# litterbox.net
KiCad netlist of a schematic drawn in EAGLE
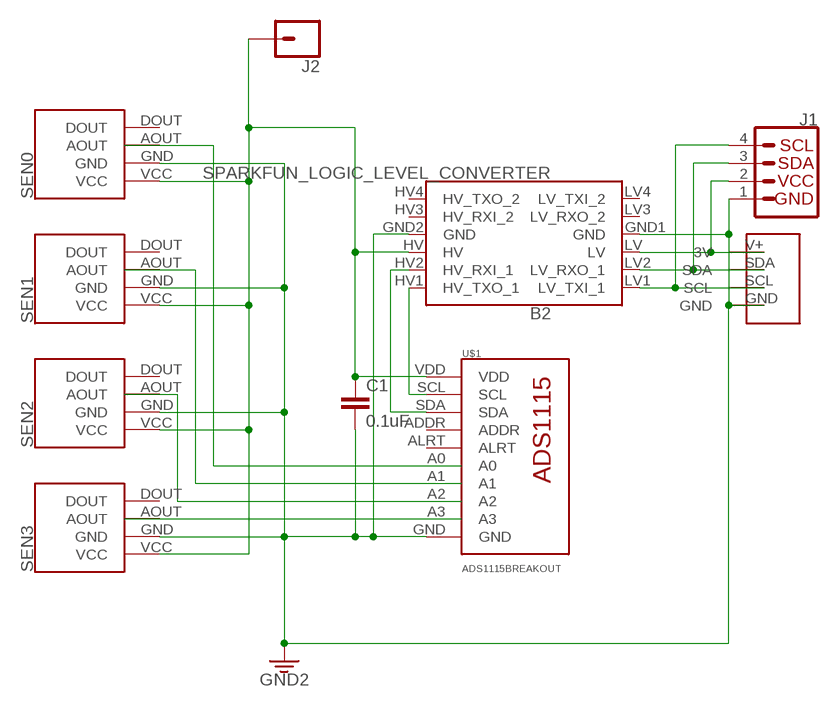
[diagram p0: schematic, sheet 1]

(export (version "E")
  (design (tool "Eeschema 10.0.6"))
  (components
    (comp (ref "B2")
      (value "SPARKFUN_LOGIC_LEVEL_CONVERTER")
      (footprint "eagle-import:SPARKFUN_LOGIC_LEVEL_CONVERTER")
      (libsource (lib "eagle-import") (part "SPARKFUN_LOGIC_LEVEL_CONVERTER"))
    )
    (comp (ref "C1")
      (value "0.1uF")
      (footprint "eagle-import:CAP-PTH-SMALL-KIT")
      (libsource (lib "eagle-import") (part "0.1UF-KIT-EZ-50V-20%"))
    )
    (comp (ref "J1")
      (value "QWIIC_CONNECTORJS-1MM")
      (footprint "eagle-import:1X04_1MM_RA")
      (libsource (lib "eagle-import") (part "QWIIC_CONNECTORJS-1MM"))
    )
    (comp (ref "J2")
      (value "CONN_01")
      (footprint "eagle-import:1X01")
      (libsource (lib "eagle-import") (part "CONN_01"))
    )
    (comp (ref "SEN0")
      (value "MQ-SENSOR-BREAKOUT")
      (footprint "eagle-import:MQ-SENSOR-BREAKOUT")
      (libsource (lib "eagle-import") (part "MQ-SENSOR-BREAKOUT"))
    )
    (comp (ref "SEN1")
      (value "MQ-SENSOR-BREAKOUT")
      (footprint "eagle-import:MQ-SENSOR-BREAKOUT")
      (libsource (lib "eagle-import") (part "MQ-SENSOR-BREAKOUT"))
    )
    (comp (ref "SEN2")
      (value "MQ-SENSOR-BREAKOUT")
      (footprint "eagle-import:MQ-SENSOR-BREAKOUT")
      (libsource (lib "eagle-import") (part "MQ-SENSOR-BREAKOUT"))
    )
    (comp (ref "SEN3")
      (value "MQ-SENSOR-BREAKOUT")
      (footprint "eagle-import:MQ-SENSOR-BREAKOUT")
      (libsource (lib "eagle-import") (part "MQ-SENSOR-BREAKOUT"))
    )
    (comp (ref "U$1")
      (value "ADS1115BREAKOUT")
      (footprint "eagle-import:ADS1115BREAKOUT")
      (libsource (lib "eagle-import") (part "ADS1115BREAKOUT"))
    )
    (comp (ref "U$2")
      (value "I2CHEADER")
      (footprint "eagle-import:I2CHEADER")
      (libsource (lib "eagle-import") (part "I2CHEADER"))
    )
  )
  (nets
    (net (code "1") (name "GND2") (class "Default")
      (node (ref "B2") (pin "GND1") (pinfunction "GND_GND1") (pintype "power_in"))
      (node (ref "B2") (pin "GND2") (pinfunction "GND_GND2") (pintype "power_in"))
      (node (ref "C1") (pin "2") (pinfunction "2_2") (pintype "passive"))
      (node (ref "J1") (pin "1") (pinfunction "GND_1") (pintype "power_in"))
      (node (ref "SEN0") (pin "GND") (pinfunction "GND_GND") (pintype "power_in"))
      (node (ref "SEN1") (pin "GND") (pinfunction "GND_GND") (pintype "power_in"))
      (node (ref "SEN2") (pin "GND") (pinfunction "GND_GND") (pintype "power_in"))
      (node (ref "SEN3") (pin "GND") (pinfunction "GND_GND") (pintype "power_in"))
      (node (ref "U$1") (pin "GND") (pinfunction "GND_GND") (pintype "power_in"))
      (node (ref "U$2") (pin "GND") (pinfunction "GND_GND") (pintype "power_in"))
    )
    (net (code "2") (name "Net-(B2-HV_RXI_1)") (class "Default")
      (node (ref "B2") (pin "HV2") (pinfunction "HV_RXI_1_HV2") (pintype "bidirectional"))
      (node (ref "U$1") (pin "SDA") (pinfunction "SDA_SDA") (pintype "bidirectional"))
    )
    (net (code "3") (name "Net-(B2-HV_TXO_1)") (class "Default")
      (node (ref "B2") (pin "HV1") (pinfunction "HV_TXO_1_HV1") (pintype "bidirectional"))
      (node (ref "U$1") (pin "SCL") (pinfunction "SCL_SCL") (pintype "bidirectional"))
    )
    (net (code "4") (name "Net-(B2-LV_RXO_1)") (class "Default")
      (node (ref "B2") (pin "LV2") (pinfunction "LV_RXO_1_LV2") (pintype "bidirectional"))
      (node (ref "J1") (pin "3") (pinfunction "SDA_3") (pintype "passive"))
      (node (ref "U$2") (pin "SDA") (pinfunction "SDA_SDA") (pintype "bidirectional"))
    )
    (net (code "5") (name "Net-(B2-LV_TXI_1)") (class "Default")
      (node (ref "B2") (pin "LV1") (pinfunction "LV_TXI_1_LV1") (pintype "bidirectional"))
      (node (ref "J1") (pin "4") (pinfunction "SCL_4") (pintype "passive"))
      (node (ref "U$2") (pin "SCL") (pinfunction "SCL_SCL") (pintype "bidirectional"))
    )
    (net (code "6") (name "Net-(B2-PadHV)") (class "Default")
      (node (ref "B2") (pin "HV") (pinfunction "HV_HV") (pintype "power_in"))
      (node (ref "C1") (pin "1") (pinfunction "1_1") (pintype "passive"))
      (node (ref "J2") (pin "1") (pinfunction "1_1") (pintype "passive"))
      (node (ref "SEN0") (pin "VCC") (pinfunction "VCC_VCC") (pintype "power_in"))
      (node (ref "SEN1") (pin "VCC") (pinfunction "VCC_VCC") (pintype "power_in"))
      (node (ref "SEN2") (pin "VCC") (pinfunction "VCC_VCC") (pintype "power_in"))
      (node (ref "SEN3") (pin "VCC") (pinfunction "VCC_VCC") (pintype "power_in"))
      (node (ref "U$1") (pin "VDD") (pinfunction "VDD_VDD") (pintype "power_in"))
    )
    (net (code "7") (name "Net-(J1-VCC)") (class "Default")
      (node (ref "B2") (pin "LV") (pinfunction "LV_LV") (pintype "power_in"))
      (node (ref "J1") (pin "2") (pinfunction "VCC_2") (pintype "power_in"))
      (node (ref "U$2") (pin "V+") (pinfunction "3V_V+") (pintype "power_in"))
    )
    (net (code "8") (name "Net-(SEN0-PadAOUT)") (class "Default")
      (node (ref "SEN0") (pin "AOUT") (pinfunction "AOUT_AOUT") (pintype "output"))
      (node (ref "U$1") (pin "A0") (pinfunction "A0_A0") (pintype "input"))
    )
    (net (code "9") (name "Net-(SEN1-PadAOUT)") (class "Default")
      (node (ref "SEN1") (pin "AOUT") (pinfunction "AOUT_AOUT") (pintype "output"))
      (node (ref "U$1") (pin "A1") (pinfunction "A1_A1") (pintype "input"))
    )
    (net (code "10") (name "Net-(SEN2-PadAOUT)") (class "Default")
      (node (ref "SEN2") (pin "AOUT") (pinfunction "AOUT_AOUT") (pintype "output"))
      (node (ref "U$1") (pin "A2") (pinfunction "A2_A2") (pintype "input"))
    )
    (net (code "11") (name "Net-(SEN3-PadAOUT)") (class "Default")
      (node (ref "SEN3") (pin "AOUT") (pinfunction "AOUT_AOUT") (pintype "output"))
      (node (ref "U$1") (pin "A3") (pinfunction "A3_A3") (pintype "input"))
    )
    (net (code "12") (name "unconnected-(B2-HV_RXI_2-PadHV3)") (class "Default")
      (node (ref "B2") (pin "HV3") (pinfunction "HV_RXI_2_HV3") (pintype "bidirectional"))
    )
    (net (code "13") (name "unconnected-(B2-HV_TXO_2-PadHV4)") (class "Default")
      (node (ref "B2") (pin "HV4") (pinfunction "HV_TXO_2_HV4") (pintype "bidirectional"))
    )
    (net (code "14") (name "unconnected-(B2-LV_RXO_2-PadLV3)") (class "Default")
      (node (ref "B2") (pin "LV3") (pinfunction "LV_RXO_2_LV3") (pintype "bidirectional"))
    )
    (net (code "15") (name "unconnected-(B2-LV_TXI_2-PadLV4)") (class "Default")
      (node (ref "B2") (pin "LV4") (pinfunction "LV_TXI_2_LV4") (pintype "bidirectional"))
    )
    (net (code "16") (name "unconnected-(SEN0-PadDOUT)") (class "Default")
      (node (ref "SEN0") (pin "DOUT") (pinfunction "DOUT_DOUT") (pintype "output"))
    )
    (net (code "17") (name "unconnected-(SEN1-PadDOUT)") (class "Default")
      (node (ref "SEN1") (pin "DOUT") (pinfunction "DOUT_DOUT") (pintype "output"))
    )
    (net (code "18") (name "unconnected-(SEN2-PadDOUT)") (class "Default")
      (node (ref "SEN2") (pin "DOUT") (pinfunction "DOUT_DOUT") (pintype "output"))
    )
    (net (code "19") (name "unconnected-(SEN3-PadDOUT)") (class "Default")
      (node (ref "SEN3") (pin "DOUT") (pinfunction "DOUT_DOUT") (pintype "output"))
    )
    (net (code "20") (name "unconnected-(U$1-PadADDR)") (class "Default")
      (node (ref "U$1") (pin "ADDR") (pinfunction "ADDR_ADDR") (pintype "input"))
    )
    (net (code "21") (name "unconnected-(U$1-PadALRT)") (class "Default")
      (node (ref "U$1") (pin "ALRT") (pinfunction "ALRT_ALRT") (pintype "output"))
    )
  )
)
